# 02-Antenna_Supervisor.net
KiCad netlist of a schematic drawn in Altium Designer
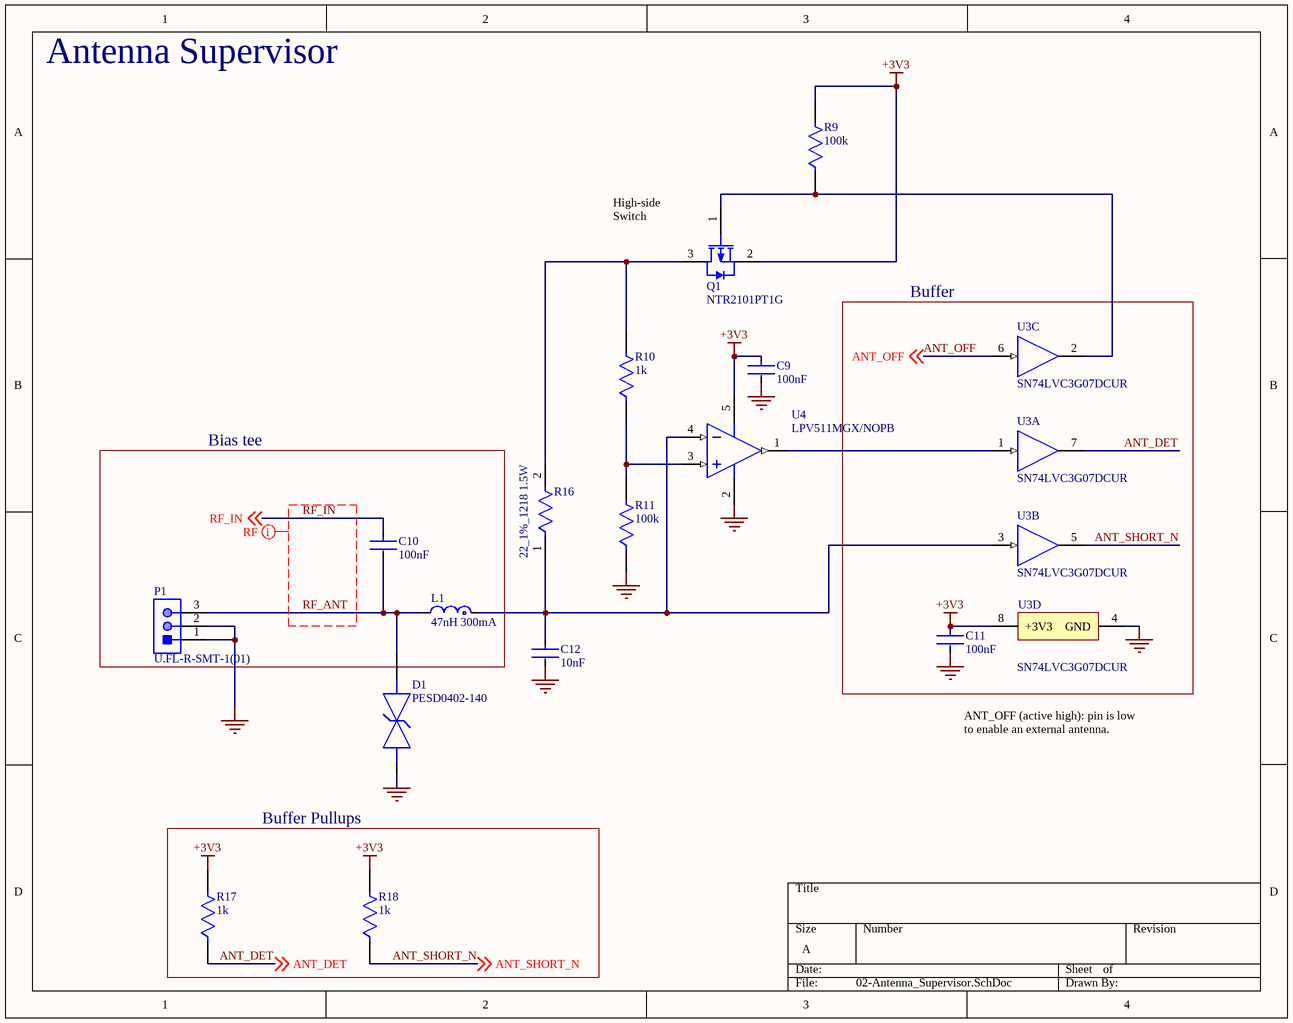
[diagram p0: 02-Antenna_Supervisor.SchDoc]

(export (version "E")
  (design (tool "Eeschema 10.0.6"))
  (components
    (comp (ref "C9")
      (value "100nF")
      (footprint "FP-0402-L_1_0_0_05-W_0_5-IPC_B")
      (description "None")
      (fields (field (name "TOLERANCE") "10%"))
      (libsource (lib "Altium Content Vault") (part "b4654b650e69147ec39a6b967a45e02"))
    )
    (comp (ref "C10")
      (value "100nF")
      (footprint "FP-0402-L_1_0_0_05-W_0_5-IPC_B")
      (description "None")
      (fields (field (name "TOLERANCE") "10%"))
      (libsource (lib "Altium Content Vault") (part "b4654b650e69147ec39a6b967a45e02"))
    )
    (comp (ref "C11")
      (value "100nF")
      (footprint "FP-0402-L_1_0_0_05-W_0_5-IPC_B")
      (description "None")
      (fields (field (name "TOLERANCE") "10%"))
      (libsource (lib "Altium Content Vault") (part "b4654b650e69147ec39a6b967a45e02"))
    )
    (comp (ref "C12")
      (value "10nF")
      (footprint "FP-GRM033-0_03-IPC_B")
      (description "Chip Multilayer Ceramic Capacitors for General Purpose, 0201, 10000pF, X7R, 15%, 10%, 16V")
      (fields (field (name "TOLERANCE") "10%"))
      (libsource (lib "Altium Content Vault") (part "b4654b650e69147ec39a6b967a45e02"))
    )
    (comp (ref "D1")
      (value "PESD0402-140")
      (footprint "FP-PESD0402-MFG")
      (description "TVS DIODE 14V 40V 0402")
      (fields
        (field (name "OCTOPART") "https://octopart.com/pesd0402-140-littelfuse-74215061")
        (field (name "MANUFACTURER") "Littelfuse Inc.")
      )
      (libsource (lib "Altium Content Vault") (part "edccc070dd5cba1f9372128faf3915e"))
    )
    (comp (ref "L1")
      (value "47nH 300mA")
      (footprint "FP-LQG15HH_02-IPC_B")
      (description "Multilayer type RF Inductor 47nH ±5% 0.72Ω 300mA 0402")
      (fields (field (name "TOLERANCE") "5%"))
      (libsource (lib "Altium Content Vault") (part "4cc4b267dca4c8e51f7102f422741d8"))
    )
    (comp (ref "P1")
      (value "U.FL-R-SMT-1(01)")
      (footprint "HRS-U.FL-R-SMT-3_V")
      (description "Ultra Small Coaxial Connector, 6 GHz, -40 to 90 degC, 3-Pin SMD, RoHS, Bulk")
      (fields (field (name "MANUFACTURER") "Hirose Electric"))
      (libsource (lib "Altium Content Vault") (part "CN-1P-M-R3"))
    )
    (comp (ref "Q1")
      (value "NTR2101PT1G")
      (footprint "ONSC-SOT-23-3-318-08_V")
      (description "Small Signal MOSFET, -8 V, -3.7 A, Single P-Channel, 3-Pin SOT-23, Pb-Free, Tape and Reel")
      (fields (field (name "MANUFACTURER") "On Semiconductor"))
      (libsource (lib "Altium Content Vault") (part "ONSC-PMOS-G1S2D3-3_D"))
    )
    (comp (ref "R9")
      (value "100k")
      (footprint "FP-RMCF0402-IPC_C")
      (description "100kΩ ±1% 0.063W 0402 Thick Film Chip Resistor AEC-Q200 compliant")
      (fields (field (name "TOLERANCE") "1%"))
      (libsource (lib "Altium Content Vault") (part "1029c3af85768c4190bb7ad29bc67b5"))
    )
    (comp (ref "R10")
      (value "1k")
      (footprint "FP-RMCF0402-MFG")
      (description "1kΩ ±1% 0.063W 0402 Thick Film Chip Resistor AEC-Q200 compliant")
      (fields (field (name "TOLERANCE") "1%"))
      (libsource (lib "Altium Content Vault") (part "1029c3af85768c4190bb7ad29bc67b5"))
    )
    (comp (ref "R11")
      (value "100k")
      (footprint "FP-RMCF0402-IPC_C")
      (description "100kΩ ±1% 0.063W 0402 Thick Film Chip Resistor AEC-Q200 compliant")
      (fields (field (name "TOLERANCE") "1%"))
      (libsource (lib "Altium Content Vault") (part "1029c3af85768c4190bb7ad29bc67b5"))
    )
    (comp (ref "R16")
      (value "22_1%_1218 1.5W")
      (footprint "FP-CRCW1218-HPe3-MFG")
      (description "RES Thick Film, 22.6Ω, 1%, 1.5W, 100ppm/°C, 1218")
      (fields (field (name "TOLERANCE") "1%"))
      (libsource (lib "") (part "1029c3af85768c4190bb7ad29bc67b5_1"))
    )
    (comp (ref "R17")
      (value "1k")
      (footprint "FP-RMCF0402-MFG")
      (description "1kΩ ±1% 0.063W 0402 Thick Film Chip Resistor AEC-Q200 compliant")
      (fields (field (name "TOLERANCE") "1%"))
      (libsource (lib "Altium Content Vault") (part "1029c3af85768c4190bb7ad29bc67b5"))
    )
    (comp (ref "R18")
      (value "1k")
      (footprint "FP-RMCF0402-MFG")
      (description "1kΩ ±1% 0.063W 0402 Thick Film Chip Resistor AEC-Q200 compliant")
      (fields (field (name "TOLERANCE") "1%"))
      (libsource (lib "Altium Content Vault") (part "1029c3af85768c4190bb7ad29bc67b5"))
    )
    (comp (ref "U3")
      (value "SN74LVC3G07DCUR")
      (footprint "DCU0008A_N")
      (description "Triple Buffer/Driver With Open-Drain Output, DCU0008A, LARGE T&R")
      (fields
        (field (name "GENERIC PART NUMBER") "SN74LVC3G07")
        (field (name "MANUFACTURER") "Texas Instruments")
      )
      (libsource (lib "Altium Content Vault") (part "TI-SN74XXX3G0X-XX-8"))
    )
    (comp (ref "U4")
      (value "LPV511MGX/NOPB")
      (footprint "DCK0005A_N")
      (description "micropower Rail-to-Rail Input and Output Operational Amplifier, 5-pin SC-70, Pb-Free")
      (fields (field (name "MANUFACTURER") "Texas Instruments"))
      (libsource (lib "Altium Content Vault") (part "AMP-OPA-LM7121-5"))
    )
  )
  (nets
    (net (code "1") (name "+3V3") (class "Default")
      (node (ref "C11") (pin "1") (pinfunction "1_1") (pintype "passive"))
      (node (ref "C9") (pin "1") (pinfunction "1_1") (pintype "passive"))
      (node (ref "Q1") (pin "2") (pinfunction "S_2") (pintype "passive"))
      (node (ref "R17") (pin "2") (pinfunction "2_2") (pintype "passive"))
      (node (ref "R18") (pin "2") (pinfunction "2_2") (pintype "passive"))
      (node (ref "R9") (pin "2") (pinfunction "2_2") (pintype "passive"))
      (node (ref "U3") (pin "8") (pinfunction "VCC_8") (pintype "power_in"))
      (node (ref "U4") (pin "5") (pinfunction "V+_5") (pintype "power_in"))
    )
    (net (code "2") (name "/RF_ANT") (class "Default")
      (node (ref "C10") (pin "2") (pinfunction "2_2") (pintype "passive"))
      (node (ref "D1") (pin "2") (pinfunction "2_2") (pintype "passive"))
      (node (ref "L1") (pin "2") (pinfunction "2_2") (pintype "passive"))
      (node (ref "P1") (pin "3") (pinfunction "3_3") (pintype "passive"))
    )
    (net (code "3") (name "ANT_DET") (class "Default")
      (node (ref "R17") (pin "1") (pinfunction "1_1") (pintype "passive"))
      (node (ref "U3") (pin "7") (pinfunction "1Y_7") (pintype "open_collector"))
    )
    (net (code "4") (name "ANT_OFF") (class "Default")
      (node (ref "U3") (pin "6") (pinfunction "3A_6") (pintype "input"))
    )
    (net (code "5") (name "ANT_SHORT_N") (class "Default")
      (node (ref "R18") (pin "1") (pinfunction "1_1") (pintype "passive"))
      (node (ref "U3") (pin "5") (pinfunction "2Y_5") (pintype "open_collector"))
    )
    (net (code "6") (name "GND") (class "Default")
      (node (ref "C11") (pin "2") (pinfunction "2_2") (pintype "passive"))
      (node (ref "C12") (pin "2") (pinfunction "2_2") (pintype "passive"))
      (node (ref "C9") (pin "2") (pinfunction "2_2") (pintype "passive"))
      (node (ref "D1") (pin "1") (pinfunction "1_1") (pintype "passive"))
      (node (ref "P1") (pin "1") (pinfunction "1_1") (pintype "passive"))
      (node (ref "P1") (pin "2") (pinfunction "2_2") (pintype "passive"))
      (node (ref "R11") (pin "1") (pinfunction "1_1") (pintype "passive"))
      (node (ref "U3") (pin "4") (pinfunction "GND_4") (pintype "power_in"))
      (node (ref "U4") (pin "2") (pinfunction "V-_2") (pintype "power_in"))
    )
    (net (code "7") (name "Net-(Q1-D)") (class "Default")
      (node (ref "Q1") (pin "3") (pinfunction "D_3") (pintype "passive"))
      (node (ref "R10") (pin "2") (pinfunction "2_2") (pintype "passive"))
      (node (ref "R16") (pin "2") (pinfunction "2_2") (pintype "passive"))
    )
    (net (code "8") (name "Net-(Q1-G)") (class "Default")
      (node (ref "Q1") (pin "1") (pinfunction "G_1") (pintype "passive"))
      (node (ref "R9") (pin "1") (pinfunction "1_1") (pintype "passive"))
      (node (ref "U3") (pin "2") (pinfunction "3Y_2") (pintype "open_collector"))
    )
    (net (code "9") (name "Net-(U3A-1A)") (class "Default")
      (node (ref "U3") (pin "1") (pinfunction "1A_1") (pintype "input"))
      (node (ref "U4") (pin "1") (pinfunction "OUT_1") (pintype "output"))
    )
    (net (code "10") (name "Net-(U3B-2A)") (class "Default")
      (node (ref "C12") (pin "1") (pinfunction "1_1") (pintype "passive"))
      (node (ref "L1") (pin "1") (pinfunction "1_1") (pintype "passive"))
      (node (ref "R16") (pin "1") (pinfunction "1_1") (pintype "passive"))
      (node (ref "U3") (pin "3") (pinfunction "2A_3") (pintype "input"))
      (node (ref "U4") (pin "4") (pinfunction "IN-_4") (pintype "input"))
    )
    (net (code "11") (name "Net-(U4-IN+)") (class "Default")
      (node (ref "R10") (pin "1") (pinfunction "1_1") (pintype "passive"))
      (node (ref "R11") (pin "2") (pinfunction "2_2") (pintype "passive"))
      (node (ref "U4") (pin "3") (pinfunction "IN+_3") (pintype "input"))
    )
    (net (code "12") (name "RF_IN") (class "Default")
      (node (ref "C10") (pin "1") (pinfunction "1_1") (pintype "passive"))
    )
  )
)
